# MicroStepper375.net
KiCad netlist of a schematic drawn in EAGLE
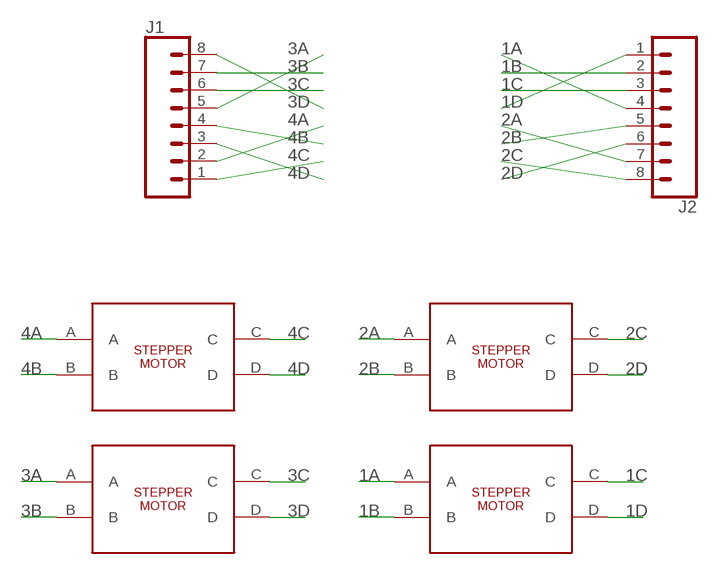
[diagram p0: schematic, sheet 1]

(export (version "E")
  (design (tool "Eeschema 10.0.6"))
  (components
    (comp (ref "J1")
      (value "CONN_08NO_SILK_FEMALE_PTH")
      (footprint "eagle-import:1X08_NO_SILK")
      (libsource (lib "eagle-import") (part "CONN_08NO_SILK_FEMALE_PTH"))
    )
    (comp (ref "J2")
      (value "CONN_08NO_SILK_FEMALE_PTH")
      (footprint "eagle-import:1X08_NO_SILK")
      (libsource (lib "eagle-import") (part "CONN_08NO_SILK_FEMALE_PTH"))
    )
    (comp (ref "U$1")
      (value "MICRO_STEPPER_375X375")
      (footprint "eagle-import:MICRO_STEPPER_375X375")
      (libsource (lib "eagle-import") (part "MICRO_STEPPER_375X375"))
    )
    (comp (ref "U$2")
      (value "MICRO_STEPPER_375X375")
      (footprint "eagle-import:MICRO_STEPPER_375X375")
      (libsource (lib "eagle-import") (part "MICRO_STEPPER_375X375"))
    )
    (comp (ref "U$3")
      (value "MICRO_STEPPER_375X375")
      (footprint "eagle-import:MICRO_STEPPER_375X375")
      (libsource (lib "eagle-import") (part "MICRO_STEPPER_375X375"))
    )
    (comp (ref "U$4")
      (value "MICRO_STEPPER_375X375")
      (footprint "eagle-import:MICRO_STEPPER_375X375")
      (libsource (lib "eagle-import") (part "MICRO_STEPPER_375X375"))
    )
  )
  (nets
    (net (code "1") (name "/1A") (class "Default")
      (node (ref "J2") (pin "4") (pinfunction "4_4") (pintype "passive"))
      (node (ref "U$4") (pin "A") (pinfunction "A_A") (pintype "bidirectional"))
    )
    (net (code "2") (name "/1B") (class "Default")
      (node (ref "J2") (pin "2") (pinfunction "2_2") (pintype "passive"))
      (node (ref "U$4") (pin "B") (pinfunction "B_B") (pintype "bidirectional"))
    )
    (net (code "3") (name "/1C") (class "Default")
      (node (ref "J2") (pin "3") (pinfunction "3_3") (pintype "passive"))
      (node (ref "U$4") (pin "C") (pinfunction "C_C") (pintype "bidirectional"))
    )
    (net (code "4") (name "/1D") (class "Default")
      (node (ref "J2") (pin "1") (pinfunction "1_1") (pintype "passive"))
      (node (ref "U$4") (pin "D") (pinfunction "D_D") (pintype "bidirectional"))
    )
    (net (code "5") (name "/2A") (class "Default")
      (node (ref "J2") (pin "7") (pinfunction "7_7") (pintype "passive"))
      (node (ref "U$3") (pin "A") (pinfunction "A_A") (pintype "bidirectional"))
    )
    (net (code "6") (name "/2B") (class "Default")
      (node (ref "J2") (pin "5") (pinfunction "5_5") (pintype "passive"))
      (node (ref "U$3") (pin "B") (pinfunction "B_B") (pintype "bidirectional"))
    )
    (net (code "7") (name "/2C") (class "Default")
      (node (ref "J2") (pin "8") (pinfunction "8_8") (pintype "passive"))
      (node (ref "U$3") (pin "C") (pinfunction "C_C") (pintype "bidirectional"))
    )
    (net (code "8") (name "/2D") (class "Default")
      (node (ref "J2") (pin "6") (pinfunction "6_6") (pintype "passive"))
      (node (ref "U$3") (pin "D") (pinfunction "D_D") (pintype "bidirectional"))
    )
    (net (code "9") (name "/3A") (class "Default")
      (node (ref "J1") (pin "5") (pinfunction "5_5") (pintype "passive"))
      (node (ref "U$2") (pin "A") (pinfunction "A_A") (pintype "bidirectional"))
    )
    (net (code "10") (name "/3B") (class "Default")
      (node (ref "J1") (pin "7") (pinfunction "7_7") (pintype "passive"))
      (node (ref "U$2") (pin "B") (pinfunction "B_B") (pintype "bidirectional"))
    )
    (net (code "11") (name "/3C") (class "Default")
      (node (ref "J1") (pin "6") (pinfunction "6_6") (pintype "passive"))
      (node (ref "U$2") (pin "C") (pinfunction "C_C") (pintype "bidirectional"))
    )
    (net (code "12") (name "/3D") (class "Default")
      (node (ref "J1") (pin "8") (pinfunction "8_8") (pintype "passive"))
      (node (ref "U$2") (pin "D") (pinfunction "D_D") (pintype "bidirectional"))
    )
    (net (code "13") (name "/4A") (class "Default")
      (node (ref "J1") (pin "2") (pinfunction "2_2") (pintype "passive"))
      (node (ref "U$1") (pin "A") (pinfunction "A_A") (pintype "bidirectional"))
    )
    (net (code "14") (name "/4B") (class "Default")
      (node (ref "J1") (pin "4") (pinfunction "4_4") (pintype "passive"))
      (node (ref "U$1") (pin "B") (pinfunction "B_B") (pintype "bidirectional"))
    )
    (net (code "15") (name "/4C") (class "Default")
      (node (ref "J1") (pin "1") (pinfunction "1_1") (pintype "passive"))
      (node (ref "U$1") (pin "C") (pinfunction "C_C") (pintype "bidirectional"))
    )
    (net (code "16") (name "/4D") (class "Default")
      (node (ref "J1") (pin "3") (pinfunction "3_3") (pintype "passive"))
      (node (ref "U$1") (pin "D") (pinfunction "D_D") (pintype "bidirectional"))
    )
  )
)
